# unixtimeclock.net
KiCad netlist of a schematic drawn in EAGLE
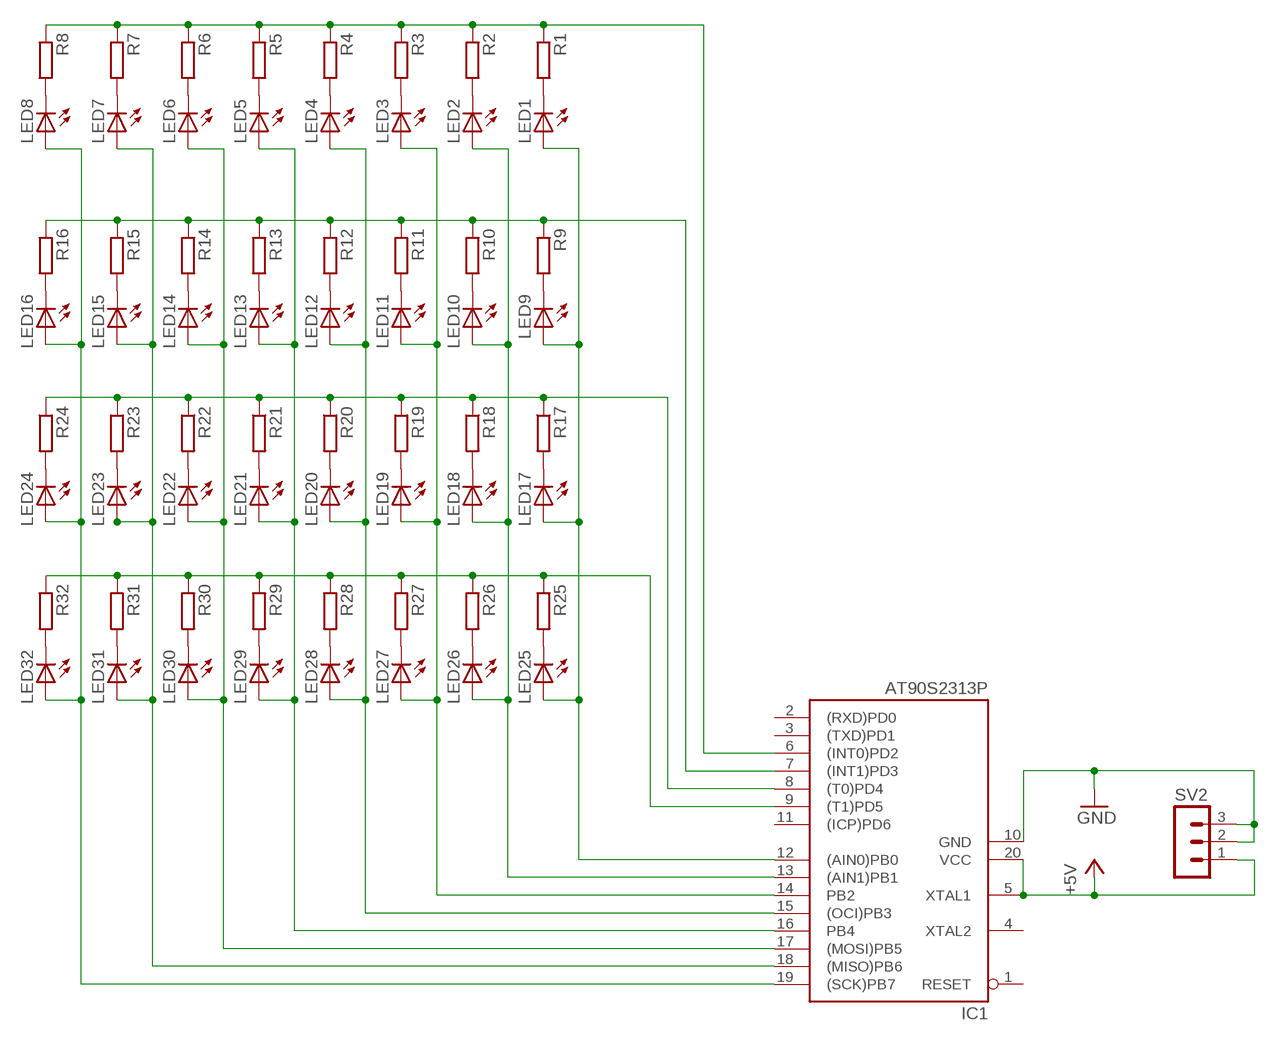
[diagram p0: schematic, sheet 1]

(export (version "E")
  (design (tool "Eeschema 10.0.6"))
  (components
    (comp (ref "IC1")
      (value "AT90S2313P")
      (footprint "eagle-import:DIL20")
      (libsource (lib "eagle-import") (part "AT90S2313P"))
    )
    (comp (ref "LED1")
      (value "LED5MM")
      (footprint "eagle-import:LED5MM")
      (libsource (lib "eagle-import") (part "LED5MM"))
    )
    (comp (ref "LED2")
      (value "LED5MM")
      (footprint "eagle-import:LED5MM")
      (libsource (lib "eagle-import") (part "LED5MM"))
    )
    (comp (ref "LED3")
      (value "LED5MM")
      (footprint "eagle-import:LED5MM")
      (libsource (lib "eagle-import") (part "LED5MM"))
    )
    (comp (ref "LED4")
      (value "LED5MM")
      (footprint "eagle-import:LED5MM")
      (libsource (lib "eagle-import") (part "LED5MM"))
    )
    (comp (ref "LED5")
      (value "LED5MM")
      (footprint "eagle-import:LED5MM")
      (libsource (lib "eagle-import") (part "LED5MM"))
    )
    (comp (ref "LED6")
      (value "LED5MM")
      (footprint "eagle-import:LED5MM")
      (libsource (lib "eagle-import") (part "LED5MM"))
    )
    (comp (ref "LED7")
      (value "LED5MM")
      (footprint "eagle-import:LED5MM")
      (libsource (lib "eagle-import") (part "LED5MM"))
    )
    (comp (ref "LED8")
      (value "LED5MM")
      (footprint "eagle-import:LED5MM")
      (libsource (lib "eagle-import") (part "LED5MM"))
    )
    (comp (ref "LED9")
      (value "LED5MM")
      (footprint "eagle-import:LED5MM")
      (libsource (lib "eagle-import") (part "LED5MM"))
    )
    (comp (ref "LED10")
      (value "LED5MM")
      (footprint "eagle-import:LED5MM")
      (libsource (lib "eagle-import") (part "LED5MM"))
    )
    (comp (ref "LED11")
      (value "LED5MM")
      (footprint "eagle-import:LED5MM")
      (libsource (lib "eagle-import") (part "LED5MM"))
    )
    (comp (ref "LED12")
      (value "LED5MM")
      (footprint "eagle-import:LED5MM")
      (libsource (lib "eagle-import") (part "LED5MM"))
    )
    (comp (ref "LED13")
      (value "LED5MM")
      (footprint "eagle-import:LED5MM")
      (libsource (lib "eagle-import") (part "LED5MM"))
    )
    (comp (ref "LED14")
      (value "LED5MM")
      (footprint "eagle-import:LED5MM")
      (libsource (lib "eagle-import") (part "LED5MM"))
    )
    (comp (ref "LED15")
      (value "LED5MM")
      (footprint "eagle-import:LED5MM")
      (libsource (lib "eagle-import") (part "LED5MM"))
    )
    (comp (ref "LED16")
      (value "LED5MM")
      (footprint "eagle-import:LED5MM")
      (libsource (lib "eagle-import") (part "LED5MM"))
    )
    (comp (ref "LED17")
      (value "LED5MM")
      (footprint "eagle-import:LED5MM")
      (libsource (lib "eagle-import") (part "LED5MM"))
    )
    (comp (ref "LED18")
      (value "LED5MM")
      (footprint "eagle-import:LED5MM")
      (libsource (lib "eagle-import") (part "LED5MM"))
    )
    (comp (ref "LED19")
      (value "LED5MM")
      (footprint "eagle-import:LED5MM")
      (libsource (lib "eagle-import") (part "LED5MM"))
    )
    (comp (ref "LED20")
      (value "LED5MM")
      (footprint "eagle-import:LED5MM")
      (libsource (lib "eagle-import") (part "LED5MM"))
    )
    (comp (ref "LED21")
      (value "LED5MM")
      (footprint "eagle-import:LED5MM")
      (libsource (lib "eagle-import") (part "LED5MM"))
    )
    (comp (ref "LED22")
      (value "LED5MM")
      (footprint "eagle-import:LED5MM")
      (libsource (lib "eagle-import") (part "LED5MM"))
    )
    (comp (ref "LED23")
      (value "LED5MM")
      (footprint "eagle-import:LED5MM")
      (libsource (lib "eagle-import") (part "LED5MM"))
    )
    (comp (ref "LED24")
      (value "LED5MM")
      (footprint "eagle-import:LED5MM")
      (libsource (lib "eagle-import") (part "LED5MM"))
    )
    (comp (ref "LED25")
      (value "LED5MM")
      (footprint "eagle-import:LED5MM")
      (libsource (lib "eagle-import") (part "LED5MM"))
    )
    (comp (ref "LED26")
      (value "LED5MM")
      (footprint "eagle-import:LED5MM")
      (libsource (lib "eagle-import") (part "LED5MM"))
    )
    (comp (ref "LED27")
      (value "LED5MM")
      (footprint "eagle-import:LED5MM")
      (libsource (lib "eagle-import") (part "LED5MM"))
    )
    (comp (ref "LED28")
      (value "LED5MM")
      (footprint "eagle-import:LED5MM")
      (libsource (lib "eagle-import") (part "LED5MM"))
    )
    (comp (ref "LED29")
      (value "LED5MM")
      (footprint "eagle-import:LED5MM")
      (libsource (lib "eagle-import") (part "LED5MM"))
    )
    (comp (ref "LED30")
      (value "LED5MM")
      (footprint "eagle-import:LED5MM")
      (libsource (lib "eagle-import") (part "LED5MM"))
    )
    (comp (ref "LED31")
      (value "LED5MM")
      (footprint "eagle-import:LED5MM")
      (libsource (lib "eagle-import") (part "LED5MM"))
    )
    (comp (ref "LED32")
      (value "LED5MM")
      (footprint "eagle-import:LED5MM")
      (libsource (lib "eagle-import") (part "LED5MM"))
    )
    (comp (ref "R1")
      (value "R-EU_0207/10")
      (footprint "eagle-import:0207_10")
      (libsource (lib "eagle-import") (part "R-EU_0207/10"))
    )
    (comp (ref "R2")
      (value "R-EU_0207/10")
      (footprint "eagle-import:0207_10")
      (libsource (lib "eagle-import") (part "R-EU_0207/10"))
    )
    (comp (ref "R3")
      (value "R-EU_0207/10")
      (footprint "eagle-import:0207_10")
      (libsource (lib "eagle-import") (part "R-EU_0207/10"))
    )
    (comp (ref "R4")
      (value "R-EU_0207/10")
      (footprint "eagle-import:0207_10")
      (libsource (lib "eagle-import") (part "R-EU_0207/10"))
    )
    (comp (ref "R5")
      (value "R-EU_0207/10")
      (footprint "eagle-import:0207_10")
      (libsource (lib "eagle-import") (part "R-EU_0207/10"))
    )
    (comp (ref "R6")
      (value "R-EU_0207/10")
      (footprint "eagle-import:0207_10")
      (libsource (lib "eagle-import") (part "R-EU_0207/10"))
    )
    (comp (ref "R7")
      (value "R-EU_0207/10")
      (footprint "eagle-import:0207_10")
      (libsource (lib "eagle-import") (part "R-EU_0207/10"))
    )
    (comp (ref "R8")
      (value "R-EU_0207/10")
      (footprint "eagle-import:0207_10")
      (libsource (lib "eagle-import") (part "R-EU_0207/10"))
    )
    (comp (ref "R9")
      (value "R-EU_0207/10")
      (footprint "eagle-import:0207_10")
      (libsource (lib "eagle-import") (part "R-EU_0207/10"))
    )
    (comp (ref "R10")
      (value "R-EU_0207/10")
      (footprint "eagle-import:0207_10")
      (libsource (lib "eagle-import") (part "R-EU_0207/10"))
    )
    (comp (ref "R11")
      (value "R-EU_0207/10")
      (footprint "eagle-import:0207_10")
      (libsource (lib "eagle-import") (part "R-EU_0207/10"))
    )
    (comp (ref "R12")
      (value "R-EU_0207/10")
      (footprint "eagle-import:0207_10")
      (libsource (lib "eagle-import") (part "R-EU_0207/10"))
    )
    (comp (ref "R13")
      (value "R-EU_0207/10")
      (footprint "eagle-import:0207_10")
      (libsource (lib "eagle-import") (part "R-EU_0207/10"))
    )
    (comp (ref "R14")
      (value "R-EU_0207/10")
      (footprint "eagle-import:0207_10")
      (libsource (lib "eagle-import") (part "R-EU_0207/10"))
    )
    (comp (ref "R15")
      (value "R-EU_0207/10")
      (footprint "eagle-import:0207_10")
      (libsource (lib "eagle-import") (part "R-EU_0207/10"))
    )
    (comp (ref "R16")
      (value "R-EU_0207/10")
      (footprint "eagle-import:0207_10")
      (libsource (lib "eagle-import") (part "R-EU_0207/10"))
    )
    (comp (ref "R17")
      (value "R-EU_0207/10")
      (footprint "eagle-import:0207_10")
      (libsource (lib "eagle-import") (part "R-EU_0207/10"))
    )
    (comp (ref "R18")
      (value "R-EU_0207/10")
      (footprint "eagle-import:0207_10")
      (libsource (lib "eagle-import") (part "R-EU_0207/10"))
    )
    (comp (ref "R19")
      (value "R-EU_0207/10")
      (footprint "eagle-import:0207_10")
      (libsource (lib "eagle-import") (part "R-EU_0207/10"))
    )
    (comp (ref "R20")
      (value "R-EU_0207/10")
      (footprint "eagle-import:0207_10")
      (libsource (lib "eagle-import") (part "R-EU_0207/10"))
    )
    (comp (ref "R21")
      (value "R-EU_0207/10")
      (footprint "eagle-import:0207_10")
      (libsource (lib "eagle-import") (part "R-EU_0207/10"))
    )
    (comp (ref "R22")
      (value "R-EU_0207/10")
      (footprint "eagle-import:0207_10")
      (libsource (lib "eagle-import") (part "R-EU_0207/10"))
    )
    (comp (ref "R23")
      (value "R-EU_0207/10")
      (footprint "eagle-import:0207_10")
      (libsource (lib "eagle-import") (part "R-EU_0207/10"))
    )
    (comp (ref "R24")
      (value "R-EU_0207/10")
      (footprint "eagle-import:0207_10")
      (libsource (lib "eagle-import") (part "R-EU_0207/10"))
    )
    (comp (ref "R25")
      (value "R-EU_0207/10")
      (footprint "eagle-import:0207_10")
      (libsource (lib "eagle-import") (part "R-EU_0207/10"))
    )
    (comp (ref "R26")
      (value "R-EU_0207/10")
      (footprint "eagle-import:0207_10")
      (libsource (lib "eagle-import") (part "R-EU_0207/10"))
    )
    (comp (ref "R27")
      (value "R-EU_0207/10")
      (footprint "eagle-import:0207_10")
      (libsource (lib "eagle-import") (part "R-EU_0207/10"))
    )
    (comp (ref "R28")
      (value "R-EU_0207/10")
      (footprint "eagle-import:0207_10")
      (libsource (lib "eagle-import") (part "R-EU_0207/10"))
    )
    (comp (ref "R29")
      (value "R-EU_0207/10")
      (footprint "eagle-import:0207_10")
      (libsource (lib "eagle-import") (part "R-EU_0207/10"))
    )
    (comp (ref "R30")
      (value "R-EU_0207/10")
      (footprint "eagle-import:0207_10")
      (libsource (lib "eagle-import") (part "R-EU_0207/10"))
    )
    (comp (ref "R31")
      (value "R-EU_0207/10")
      (footprint "eagle-import:0207_10")
      (libsource (lib "eagle-import") (part "R-EU_0207/10"))
    )
    (comp (ref "R32")
      (value "R-EU_0207/10")
      (footprint "eagle-import:0207_10")
      (libsource (lib "eagle-import") (part "R-EU_0207/10"))
    )
    (comp (ref "SV2")
      (value "MA03-1")
      (footprint "eagle-import:MA03-1")
      (libsource (lib "eagle-import") (part "MA03-1"))
    )
  )
  (nets
    (net (code "1") (name "+5V") (class "Default")
      (node (ref "IC1") (pin "20") (pinfunction "VCC_20") (pintype "power_in"))
      (node (ref "IC1") (pin "5") (pinfunction "XTAL1_5") (pintype "bidirectional"))
      (node (ref "SV2") (pin "1") (pinfunction "1_1") (pintype "passive"))
    )
    (net (code "2") (name "GND") (class "Default")
      (node (ref "IC1") (pin "10") (pinfunction "GND_10") (pintype "power_in"))
      (node (ref "SV2") (pin "2") (pinfunction "2_2") (pintype "passive"))
      (node (ref "SV2") (pin "3") (pinfunction "3_3") (pintype "passive"))
    )
    (net (code "3") (name "Net-(IC1-(AIN0)PB0)") (class "Default")
      (node (ref "IC1") (pin "12") (pinfunction "(AIN0)PB0_12") (pintype "bidirectional"))
      (node (ref "LED1") (pin "A") (pinfunction "A_A") (pintype "passive"))
      (node (ref "LED17") (pin "A") (pinfunction "A_A") (pintype "passive"))
      (node (ref "LED25") (pin "A") (pinfunction "A_A") (pintype "passive"))
      (node (ref "LED9") (pin "A") (pinfunction "A_A") (pintype "passive"))
    )
    (net (code "4") (name "Net-(IC1-(AIN1)PB1)") (class "Default")
      (node (ref "IC1") (pin "13") (pinfunction "(AIN1)PB1_13") (pintype "bidirectional"))
      (node (ref "LED10") (pin "A") (pinfunction "A_A") (pintype "passive"))
      (node (ref "LED18") (pin "A") (pinfunction "A_A") (pintype "passive"))
      (node (ref "LED2") (pin "A") (pinfunction "A_A") (pintype "passive"))
      (node (ref "LED26") (pin "A") (pinfunction "A_A") (pintype "passive"))
    )
    (net (code "5") (name "Net-(IC1-(INT0)PD2)") (class "Default")
      (node (ref "IC1") (pin "6") (pinfunction "(INT0)PD2_6") (pintype "bidirectional"))
      (node (ref "R1") (pin "1") (pinfunction "1_1") (pintype "passive"))
      (node (ref "R2") (pin "1") (pinfunction "1_1") (pintype "passive"))
      (node (ref "R3") (pin "1") (pinfunction "1_1") (pintype "passive"))
      (node (ref "R4") (pin "1") (pinfunction "1_1") (pintype "passive"))
      (node (ref "R5") (pin "1") (pinfunction "1_1") (pintype "passive"))
      (node (ref "R6") (pin "1") (pinfunction "1_1") (pintype "passive"))
      (node (ref "R7") (pin "1") (pinfunction "1_1") (pintype "passive"))
      (node (ref "R8") (pin "1") (pinfunction "1_1") (pintype "passive"))
    )
    (net (code "6") (name "Net-(IC1-(INT1)PD3)") (class "Default")
      (node (ref "IC1") (pin "7") (pinfunction "(INT1)PD3_7") (pintype "bidirectional"))
      (node (ref "R10") (pin "1") (pinfunction "1_1") (pintype "passive"))
      (node (ref "R11") (pin "1") (pinfunction "1_1") (pintype "passive"))
      (node (ref "R12") (pin "1") (pinfunction "1_1") (pintype "passive"))
      (node (ref "R13") (pin "1") (pinfunction "1_1") (pintype "passive"))
      (node (ref "R14") (pin "1") (pinfunction "1_1") (pintype "passive"))
      (node (ref "R15") (pin "1") (pinfunction "1_1") (pintype "passive"))
      (node (ref "R16") (pin "1") (pinfunction "1_1") (pintype "passive"))
      (node (ref "R9") (pin "1") (pinfunction "1_1") (pintype "passive"))
    )
    (net (code "7") (name "Net-(IC1-(MISO)PB6)") (class "Default")
      (node (ref "IC1") (pin "18") (pinfunction "(MISO)PB6_18") (pintype "bidirectional"))
      (node (ref "LED15") (pin "A") (pinfunction "A_A") (pintype "passive"))
      (node (ref "LED23") (pin "A") (pinfunction "A_A") (pintype "passive"))
      (node (ref "LED31") (pin "A") (pinfunction "A_A") (pintype "passive"))
      (node (ref "LED7") (pin "A") (pinfunction "A_A") (pintype "passive"))
    )
    (net (code "8") (name "Net-(IC1-(MOSI)PB5)") (class "Default")
      (node (ref "IC1") (pin "17") (pinfunction "(MOSI)PB5_17") (pintype "bidirectional"))
      (node (ref "LED14") (pin "A") (pinfunction "A_A") (pintype "passive"))
      (node (ref "LED22") (pin "A") (pinfunction "A_A") (pintype "passive"))
      (node (ref "LED30") (pin "A") (pinfunction "A_A") (pintype "passive"))
      (node (ref "LED6") (pin "A") (pinfunction "A_A") (pintype "passive"))
    )
    (net (code "9") (name "Net-(IC1-(OCI)PB3)") (class "Default")
      (node (ref "IC1") (pin "15") (pinfunction "(OCI)PB3_15") (pintype "bidirectional"))
      (node (ref "LED12") (pin "A") (pinfunction "A_A") (pintype "passive"))
      (node (ref "LED20") (pin "A") (pinfunction "A_A") (pintype "passive"))
      (node (ref "LED28") (pin "A") (pinfunction "A_A") (pintype "passive"))
      (node (ref "LED4") (pin "A") (pinfunction "A_A") (pintype "passive"))
    )
    (net (code "10") (name "Net-(IC1-(SCK)PB7)") (class "Default")
      (node (ref "IC1") (pin "19") (pinfunction "(SCK)PB7_19") (pintype "bidirectional"))
      (node (ref "LED16") (pin "A") (pinfunction "A_A") (pintype "passive"))
      (node (ref "LED24") (pin "A") (pinfunction "A_A") (pintype "passive"))
      (node (ref "LED32") (pin "A") (pinfunction "A_A") (pintype "passive"))
      (node (ref "LED8") (pin "A") (pinfunction "A_A") (pintype "passive"))
    )
    (net (code "11") (name "Net-(IC1-(T0)PD4)") (class "Default")
      (node (ref "IC1") (pin "8") (pinfunction "(T0)PD4_8") (pintype "bidirectional"))
      (node (ref "R17") (pin "1") (pinfunction "1_1") (pintype "passive"))
      (node (ref "R18") (pin "1") (pinfunction "1_1") (pintype "passive"))
      (node (ref "R19") (pin "1") (pinfunction "1_1") (pintype "passive"))
      (node (ref "R20") (pin "1") (pinfunction "1_1") (pintype "passive"))
      (node (ref "R21") (pin "1") (pinfunction "1_1") (pintype "passive"))
      (node (ref "R22") (pin "1") (pinfunction "1_1") (pintype "passive"))
      (node (ref "R23") (pin "1") (pinfunction "1_1") (pintype "passive"))
      (node (ref "R24") (pin "1") (pinfunction "1_1") (pintype "passive"))
    )
    (net (code "12") (name "Net-(IC1-(T1)PD5)") (class "Default")
      (node (ref "IC1") (pin "9") (pinfunction "(T1)PD5_9") (pintype "bidirectional"))
      (node (ref "R25") (pin "1") (pinfunction "1_1") (pintype "passive"))
      (node (ref "R26") (pin "1") (pinfunction "1_1") (pintype "passive"))
      (node (ref "R27") (pin "1") (pinfunction "1_1") (pintype "passive"))
      (node (ref "R28") (pin "1") (pinfunction "1_1") (pintype "passive"))
      (node (ref "R29") (pin "1") (pinfunction "1_1") (pintype "passive"))
      (node (ref "R30") (pin "1") (pinfunction "1_1") (pintype "passive"))
      (node (ref "R31") (pin "1") (pinfunction "1_1") (pintype "passive"))
      (node (ref "R32") (pin "1") (pinfunction "1_1") (pintype "passive"))
    )
    (net (code "13") (name "Net-(IC1-PB2)") (class "Default")
      (node (ref "IC1") (pin "14") (pinfunction "PB2_14") (pintype "bidirectional"))
      (node (ref "LED11") (pin "A") (pinfunction "A_A") (pintype "passive"))
      (node (ref "LED19") (pin "A") (pinfunction "A_A") (pintype "passive"))
      (node (ref "LED27") (pin "A") (pinfunction "A_A") (pintype "passive"))
      (node (ref "LED3") (pin "A") (pinfunction "A_A") (pintype "passive"))
    )
    (net (code "14") (name "Net-(IC1-PB4)") (class "Default")
      (node (ref "IC1") (pin "16") (pinfunction "PB4_16") (pintype "bidirectional"))
      (node (ref "LED13") (pin "A") (pinfunction "A_A") (pintype "passive"))
      (node (ref "LED21") (pin "A") (pinfunction "A_A") (pintype "passive"))
      (node (ref "LED29") (pin "A") (pinfunction "A_A") (pintype "passive"))
      (node (ref "LED5") (pin "A") (pinfunction "A_A") (pintype "passive"))
    )
    (net (code "15") (name "Net-(LED1-C)") (class "Default")
      (node (ref "LED1") (pin "K") (pinfunction "C_K") (pintype "passive"))
      (node (ref "R1") (pin "2") (pinfunction "2_2") (pintype "passive"))
    )
    (net (code "16") (name "Net-(LED2-C)") (class "Default")
      (node (ref "LED2") (pin "K") (pinfunction "C_K") (pintype "passive"))
      (node (ref "R2") (pin "2") (pinfunction "2_2") (pintype "passive"))
    )
    (net (code "17") (name "Net-(LED3-C)") (class "Default")
      (node (ref "LED3") (pin "K") (pinfunction "C_K") (pintype "passive"))
      (node (ref "R3") (pin "2") (pinfunction "2_2") (pintype "passive"))
    )
    (net (code "18") (name "Net-(LED4-C)") (class "Default")
      (node (ref "LED4") (pin "K") (pinfunction "C_K") (pintype "passive"))
      (node (ref "R4") (pin "2") (pinfunction "2_2") (pintype "passive"))
    )
    (net (code "19") (name "Net-(LED5-C)") (class "Default")
      (node (ref "LED5") (pin "K") (pinfunction "C_K") (pintype "passive"))
      (node (ref "R5") (pin "2") (pinfunction "2_2") (pintype "passive"))
    )
    (net (code "20") (name "Net-(LED6-C)") (class "Default")
      (node (ref "LED6") (pin "K") (pinfunction "C_K") (pintype "passive"))
      (node (ref "R6") (pin "2") (pinfunction "2_2") (pintype "passive"))
    )
    (net (code "21") (name "Net-(LED7-C)") (class "Default")
      (node (ref "LED7") (pin "K") (pinfunction "C_K") (pintype "passive"))
      (node (ref "R7") (pin "2") (pinfunction "2_2") (pintype "passive"))
    )
    (net (code "22") (name "Net-(LED8-C)") (class "Default")
      (node (ref "LED8") (pin "K") (pinfunction "C_K") (pintype "passive"))
      (node (ref "R8") (pin "2") (pinfunction "2_2") (pintype "passive"))
    )
    (net (code "23") (name "Net-(LED9-C)") (class "Default")
      (node (ref "LED9") (pin "K") (pinfunction "C_K") (pintype "passive"))
      (node (ref "R9") (pin "2") (pinfunction "2_2") (pintype "passive"))
    )
    (net (code "24") (name "Net-(LED10-C)") (class "Default")
      (node (ref "LED10") (pin "K") (pinfunction "C_K") (pintype "passive"))
      (node (ref "R10") (pin "2") (pinfunction "2_2") (pintype "passive"))
    )
    (net (code "25") (name "Net-(LED11-C)") (class "Default")
      (node (ref "LED11") (pin "K") (pinfunction "C_K") (pintype "passive"))
      (node (ref "R11") (pin "2") (pinfunction "2_2") (pintype "passive"))
    )
    (net (code "26") (name "Net-(LED12-C)") (class "Default")
      (node (ref "LED12") (pin "K") (pinfunction "C_K") (pintype "passive"))
      (node (ref "R12") (pin "2") (pinfunction "2_2") (pintype "passive"))
    )
    (net (code "27") (name "Net-(LED13-C)") (class "Default")
      (node (ref "LED13") (pin "K") (pinfunction "C_K") (pintype "passive"))
      (node (ref "R13") (pin "2") (pinfunction "2_2") (pintype "passive"))
    )
    (net (code "28") (name "Net-(LED14-C)") (class "Default")
      (node (ref "LED14") (pin "K") (pinfunction "C_K") (pintype "passive"))
      (node (ref "R14") (pin "2") (pinfunction "2_2") (pintype "passive"))
    )
    (net (code "29") (name "Net-(LED15-C)") (class "Default")
      (node (ref "LED15") (pin "K") (pinfunction "C_K") (pintype "passive"))
      (node (ref "R15") (pin "2") (pinfunction "2_2") (pintype "passive"))
    )
    (net (code "30") (name "Net-(LED16-C)") (class "Default")
      (node (ref "LED16") (pin "K") (pinfunction "C_K") (pintype "passive"))
      (node (ref "R16") (pin "2") (pinfunction "2_2") (pintype "passive"))
    )
    (net (code "31") (name "Net-(LED17-C)") (class "Default")
      (node (ref "LED17") (pin "K") (pinfunction "C_K") (pintype "passive"))
      (node (ref "R17") (pin "2") (pinfunction "2_2") (pintype "passive"))
    )
    (net (code "32") (name "Net-(LED18-C)") (class "Default")
      (node (ref "LED18") (pin "K") (pinfunction "C_K") (pintype "passive"))
      (node (ref "R18") (pin "2") (pinfunction "2_2") (pintype "passive"))
    )
    (net (code "33") (name "Net-(LED19-C)") (class "Default")
      (node (ref "LED19") (pin "K") (pinfunction "C_K") (pintype "passive"))
      (node (ref "R19") (pin "2") (pinfunction "2_2") (pintype "passive"))
    )
    (net (code "34") (name "Net-(LED20-C)") (class "Default")
      (node (ref "LED20") (pin "K") (pinfunction "C_K") (pintype "passive"))
      (node (ref "R20") (pin "2") (pinfunction "2_2") (pintype "passive"))
    )
    (net (code "35") (name "Net-(LED21-C)") (class "Default")
      (node (ref "LED21") (pin "K") (pinfunction "C_K") (pintype "passive"))
      (node (ref "R21") (pin "2") (pinfunction "2_2") (pintype "passive"))
    )
    (net (code "36") (name "Net-(LED22-C)") (class "Default")
      (node (ref "LED22") (pin "K") (pinfunction "C_K") (pintype "passive"))
      (node (ref "R22") (pin "2") (pinfunction "2_2") (pintype "passive"))
    )
    (net (code "37") (name "Net-(LED23-C)") (class "Default")
      (node (ref "LED23") (pin "K") (pinfunction "C_K") (pintype "passive"))
      (node (ref "R23") (pin "2") (pinfunction "2_2") (pintype "passive"))
    )
    (net (code "38") (name "Net-(LED24-C)") (class "Default")
      (node (ref "LED24") (pin "K") (pinfunction "C_K") (pintype "passive"))
      (node (ref "R24") (pin "2") (pinfunction "2_2") (pintype "passive"))
    )
    (net (code "39") (name "Net-(LED25-C)") (class "Default")
      (node (ref "LED25") (pin "K") (pinfunction "C_K") (pintype "passive"))
      (node (ref "R25") (pin "2") (pinfunction "2_2") (pintype "passive"))
    )
    (net (code "40") (name "Net-(LED26-C)") (class "Default")
      (node (ref "LED26") (pin "K") (pinfunction "C_K") (pintype "passive"))
      (node (ref "R26") (pin "2") (pinfunction "2_2") (pintype "passive"))
    )
    (net (code "41") (name "Net-(LED27-C)") (class "Default")
      (node (ref "LED27") (pin "K") (pinfunction "C_K") (pintype "passive"))
      (node (ref "R27") (pin "2") (pinfunction "2_2") (pintype "passive"))
    )
    (net (code "42") (name "Net-(LED28-C)") (class "Default")
      (node (ref "LED28") (pin "K") (pinfunction "C_K") (pintype "passive"))
      (node (ref "R28") (pin "2") (pinfunction "2_2") (pintype "passive"))
    )
    (net (code "43") (name "Net-(LED29-C)") (class "Default")
      (node (ref "LED29") (pin "K") (pinfunction "C_K") (pintype "passive"))
      (node (ref "R29") (pin "2") (pinfunction "2_2") (pintype "passive"))
    )
    (net (code "44") (name "Net-(LED30-C)") (class "Default")
      (node (ref "LED30") (pin "K") (pinfunction "C_K") (pintype "passive"))
      (node (ref "R30") (pin "2") (pinfunction "2_2") (pintype "passive"))
    )
    (net (code "45") (name "Net-(LED31-C)") (class "Default")
      (node (ref "LED31") (pin "K") (pinfunction "C_K") (pintype "passive"))
      (node (ref "R31") (pin "2") (pinfunction "2_2") (pintype "passive"))
    )
    (net (code "46") (name "Net-(LED32-C)") (class "Default")
      (node (ref "LED32") (pin "K") (pinfunction "C_K") (pintype "passive"))
      (node (ref "R32") (pin "2") (pinfunction "2_2") (pintype "passive"))
    )
    (net (code "47") (name "unconnected-(IC1-(ICP)PD6-Pad11)") (class "Default")
      (node (ref "IC1") (pin "11") (pinfunction "(ICP)PD6_11") (pintype "bidirectional"))
    )
    (net (code "48") (name "unconnected-(IC1-(RXD)PD0-Pad2)") (class "Default")
      (node (ref "IC1") (pin "2") (pinfunction "(RXD)PD0_2") (pintype "bidirectional"))
    )
    (net (code "49") (name "unconnected-(IC1-(TXD)PD1-Pad3)") (class "Default")
      (node (ref "IC1") (pin "3") (pinfunction "(TXD)PD1_3") (pintype "bidirectional"))
    )
    (net (code "50") (name "unconnected-(IC1-RESET-Pad1)") (class "Default")
      (node (ref "IC1") (pin "1") (pinfunction "RESET_1") (pintype "bidirectional"))
    )
    (net (code "51") (name "unconnected-(IC1-XTAL2-Pad4)") (class "Default")
      (node (ref "IC1") (pin "4") (pinfunction "XTAL2_4") (pintype "bidirectional"))
    )
  )
)
